# NSTRI.net
KiCad netlist of a schematic drawn in Altium Designer
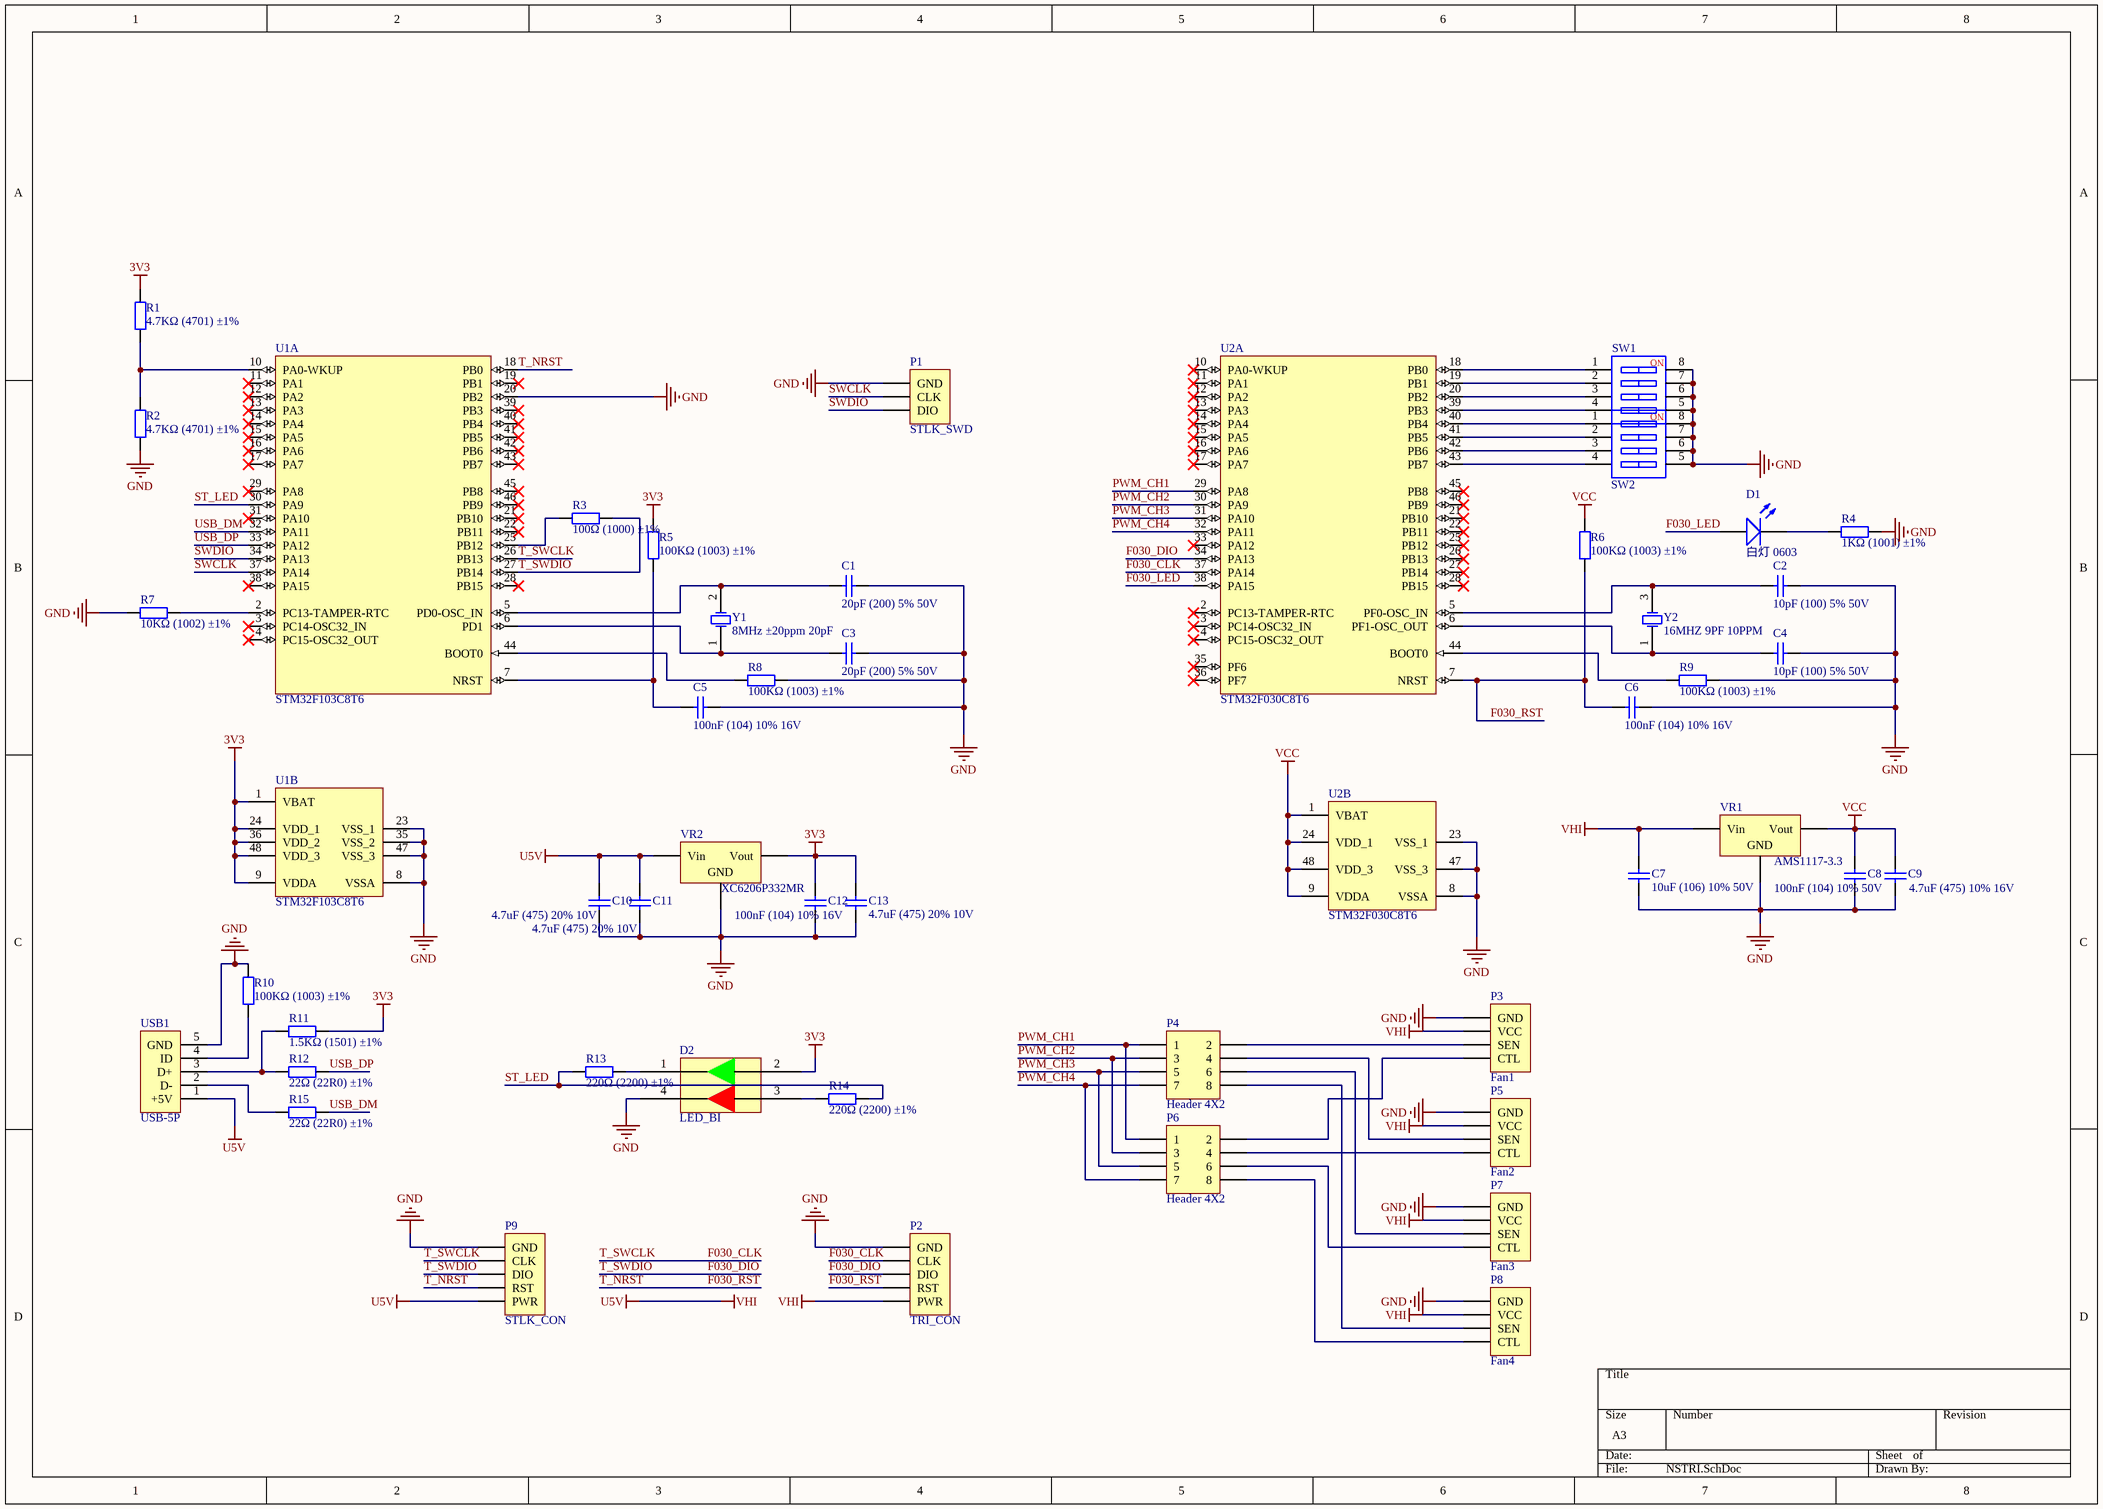
[diagram p0: NSTRI.SchDoc]

(export (version "E")
  (design (tool "Eeschema 10.0.6"))
  (components
    (comp (ref "C1")
      (value "20pF (200) 5% 50V")
      (footprint "0402_C")
      (description "贴片电容")
      (libsource (lib "Miscellaneous Devices LC") (part "0402 20pF (200) 5% 50V"))
    )
    (comp (ref "C2")
      (value "10pF (100) 5% 50V")
      (footprint "0402_C")
      (description "贴片电容")
      (libsource (lib "Miscellaneous Devices LC") (part "0402 10pF (100) 5% 50V"))
    )
    (comp (ref "C3")
      (value "20pF (200) 5% 50V")
      (footprint "0402_C")
      (description "贴片电容")
      (libsource (lib "Miscellaneous Devices LC") (part "0402 20pF (200) 5% 50V"))
    )
    (comp (ref "C4")
      (value "10pF (100) 5% 50V")
      (footprint "0402_C")
      (description "贴片电容")
      (libsource (lib "Miscellaneous Devices LC") (part "0402 10pF (100) 5% 50V"))
    )
    (comp (ref "C5")
      (value "100nF (104) 10% 16V")
      (footprint "0402_C")
      (description "贴片电容")
      (libsource (lib "Miscellaneous Devices LC") (part "0402 100nF (104) 10% 16V"))
    )
    (comp (ref "C6")
      (value "100nF (104) 10% 16V")
      (footprint "0402_C")
      (description "贴片电容")
      (libsource (lib "Miscellaneous Devices LC") (part "0402 100nF (104) 10% 16V"))
    )
    (comp (ref "C7")
      (value "10uF (106) 10% 50V")
      (footprint "1206_C")
      (description "贴片电容")
      (libsource (lib "Miscellaneous Devices LC") (part "1206 10uF (106) 10% 50V"))
    )
    (comp (ref "C8")
      (value "100nF (104) 10% 50V")
      (footprint "0603_C")
      (description "贴片电容")
      (libsource (lib "Miscellaneous Devices LC") (part "0603 100nF (104) 10% 50V"))
    )
    (comp (ref "C9")
      (value "4.7uF (475) 10% 16V")
      (footprint "0603_C")
      (description "贴片电容")
      (libsource (lib "Miscellaneous Devices LC") (part "0603 4.7uF (475) 10% 16V"))
    )
    (comp (ref "C10")
      (value "4.7uF (475) 20% 10V")
      (footprint "0402_C")
      (description "贴片电容")
      (libsource (lib "Miscellaneous Devices LC") (part "0402 4.7uF (475) 20% 10V"))
    )
    (comp (ref "C11")
      (value "4.7uF (475) 20% 10V")
      (footprint "0402_C")
      (description "贴片电容")
      (libsource (lib "Miscellaneous Devices LC") (part "0402 4.7uF (475) 20% 10V"))
    )
    (comp (ref "C12")
      (value "100nF (104) 10% 16V")
      (footprint "0402_C")
      (description "贴片电容")
      (libsource (lib "Miscellaneous Devices LC") (part "0402 100nF (104) 10% 16V"))
    )
    (comp (ref "C13")
      (value "4.7uF (475) 20% 10V")
      (footprint "0402_C")
      (description "贴片电容")
      (libsource (lib "Miscellaneous Devices LC") (part "0402 4.7uF (475) 20% 10V"))
    )
    (comp (ref "D1")
      (value "白灯 0603")
      (footprint "0603_LED_S1")
      (description "发光二极管")
      (libsource (lib "Miscellaneous Devices LC") (part "0603 白灯"))
    )
    (comp (ref "D2") (value "LED_BI") (footprint "LED_BI") (libsource (lib "ngh-util") (part "LED_BI")))
    (comp (ref "P1")
      (value "STLK_SWD")
      (footprint "HDR1X3")
      (description "Header, 3-Pin")
      (fields (field (name "PUBLISHER") "Altium Limited"))
      (libsource (lib "Miscellaneous Connectors") (part "Header 3"))
    )
    (comp (ref "P2")
      (value "TRI_CON")
      (footprint "HDR1X5")
      (description "Header, 5-Pin")
      (fields (field (name "PUBLISHER") "Altium Limited"))
      (libsource (lib "Miscellaneous Connectors") (part "Header 5"))
    )
    (comp (ref "P3")
      (value "Fan1")
      (footprint "HDR1X4")
      (description "Header, 4-Pin")
      (fields (field (name "PUBLISHER") "Altium Limited"))
      (libsource (lib "Miscellaneous Connectors") (part "Header 4"))
    )
    (comp (ref "P4")
      (value "Header 4X2")
      (footprint "HDR2X4")
      (description "Header, 4-Pin, Dual row")
      (fields (field (name "PUBLISHER") "Altium Limited"))
      (libsource (lib "Miscellaneous Connectors") (part "Header 4X2"))
    )
    (comp (ref "P5")
      (value "Fan2")
      (footprint "HDR1X4")
      (description "Header, 4-Pin")
      (fields (field (name "PUBLISHER") "Altium Limited"))
      (libsource (lib "Miscellaneous Connectors") (part "Header 4"))
    )
    (comp (ref "P6")
      (value "Header 4X2")
      (footprint "HDR2X4")
      (description "Header, 4-Pin, Dual row")
      (fields (field (name "PUBLISHER") "Altium Limited"))
      (libsource (lib "Miscellaneous Connectors") (part "Header 4X2"))
    )
    (comp (ref "P7")
      (value "Fan3")
      (footprint "HDR1X4")
      (description "Header, 4-Pin")
      (fields (field (name "PUBLISHER") "Altium Limited"))
      (libsource (lib "Miscellaneous Connectors") (part "Header 4"))
    )
    (comp (ref "P8")
      (value "Fan4")
      (footprint "HDR1X4")
      (description "Header, 4-Pin")
      (fields (field (name "PUBLISHER") "Altium Limited"))
      (libsource (lib "Miscellaneous Connectors") (part "Header 4"))
    )
    (comp (ref "P9")
      (value "STLK_CON")
      (footprint "HDR1X5")
      (description "Header, 5-Pin")
      (fields (field (name "PUBLISHER") "Altium Limited"))
      (libsource (lib "Miscellaneous Connectors") (part "Header 5"))
    )
    (comp (ref "R1")
      (value "4.7KΩ (4701) ±1%")
      (footprint "0402_R")
      (description "贴片电阻")
      (libsource (lib "Miscellaneous Devices LC") (part "0402 4.7KΩ (4701) 1%"))
    )
    (comp (ref "R2")
      (value "4.7KΩ (4701) ±1%")
      (footprint "0402_R")
      (description "贴片电阻")
      (libsource (lib "Miscellaneous Devices LC") (part "0402 4.7KΩ (4701) 1%"))
    )
    (comp (ref "R3")
      (value "100Ω (1000) ±1%")
      (footprint "0402_R")
      (description "贴片电阻")
      (libsource (lib "Miscellaneous Devices LC") (part "0402 100Ω (1000) 1%"))
    )
    (comp (ref "R4")
      (value "1KΩ (1001) ±1%")
      (footprint "0402_R")
      (description "贴片电阻")
      (libsource (lib "Miscellaneous Devices LC") (part "0402 1KΩ (1001) 1%"))
    )
    (comp (ref "R5")
      (value "100KΩ (1003) ±1%")
      (footprint "0402_R")
      (description "贴片电阻")
      (libsource (lib "Miscellaneous Devices LC") (part "0402 100KΩ (1003) 1%"))
    )
    (comp (ref "R6")
      (value "100KΩ (1003) ±1%")
      (footprint "0402_R")
      (description "贴片电阻")
      (libsource (lib "Miscellaneous Devices LC") (part "0402 100KΩ (1003) 1%"))
    )
    (comp (ref "R7")
      (value "10KΩ (1002) ±1%")
      (footprint "0402_R")
      (description "贴片电阻")
      (libsource (lib "Miscellaneous Devices LC") (part "0402 10KΩ (1002) 1%"))
    )
    (comp (ref "R8")
      (value "100KΩ (1003) ±1%")
      (footprint "0402_R")
      (description "贴片电阻")
      (libsource (lib "") (part "0402 100KΩ (1003) 1%_1"))
    )
    (comp (ref "R9")
      (value "100KΩ (1003) ±1%")
      (footprint "0402_R")
      (description "贴片电阻")
      (libsource (lib "") (part "0402 100KΩ (1003) 1%_1"))
    )
    (comp (ref "R10")
      (value "100KΩ (1003) ±1%")
      (footprint "0402_R")
      (description "贴片电阻")
      (libsource (lib "Miscellaneous Devices LC") (part "0402 100KΩ (1003) 1%"))
    )
    (comp (ref "R11")
      (value "1.5KΩ (1501) ±1%")
      (footprint "0402_R")
      (description "贴片电阻")
      (libsource (lib "Miscellaneous Devices LC") (part "0402 1.5KΩ (1501) 1%"))
    )
    (comp (ref "R12")
      (value "22Ω (22R0) ±1%")
      (footprint "0402_R")
      (description "贴片电阻")
      (libsource (lib "Miscellaneous Devices LC") (part "0402 22Ω (22R0) 1%"))
    )
    (comp (ref "R13")
      (value "220Ω (2200) ±1%")
      (footprint "0402_R")
      (description "贴片电阻")
      (libsource (lib "Miscellaneous Devices LC") (part "0402 220Ω (2200) 1%"))
    )
    (comp (ref "R14")
      (value "220Ω (2200) ±1%")
      (footprint "0402_R")
      (description "贴片电阻")
      (libsource (lib "Miscellaneous Devices LC") (part "0402 220Ω (2200) 1%"))
    )
    (comp (ref "R15")
      (value "22Ω (22R0) ±1%")
      (footprint "0402_R")
      (description "贴片电阻")
      (libsource (lib "Miscellaneous Devices LC") (part "0402 22Ω (22R0) 1%"))
    )
    (comp (ref "SW1")
      (value "CSW-4P")
      (footprint "CSW DIP-4P")
      (description "4路编码开关")
      (fields (field (name "版权归属") "源创客"))
      (libsource (lib "5.1   - 按键-开关") (part "CSW-4P"))
    )
    (comp (ref "SW2")
      (value "CSW-4P")
      (footprint "CSW DIP-4P")
      (description "4路编码开关")
      (fields (field (name "版权归属") "源创客"))
      (libsource (lib "5.1   - 按键-开关") (part "CSW-4P"))
    )
    (comp (ref "U1")
      (value "STM32F103C8T6")
      (footprint "LQFP-48_7x7x05P")
      (description "ARM")
      (libsource (lib "Miscellaneous Devices LC") (part "STM32F103C8T6"))
    )
    (comp (ref "U2")
      (value "STM32F030C8T6")
      (footprint "LQFP-48_7x7x05P")
      (description "ARM")
      (libsource (lib "STM32F030C8") (part "STM32F030C8T6"))
    )
    (comp (ref "USB1")
      (value "USB-5P")
      (footprint "USB-MICRO_D")
      (description "微型USB母座")
      (fields (field (name "版权归属") "源创客"))
      (libsource (lib "4.1   - 接口类") (part "USB-5P"))
    )
    (comp (ref "VR1")
      (value "AMS1117-3.3")
      (footprint "SOT-223")
      (description "低压差线性稳压(LDO)")
      (libsource (lib "Miscellaneous Devices LC") (part "SOT-223 AMS1117-3.3"))
    )
    (comp (ref "VR2")
      (value "XC6206P332MR")
      (footprint "SOT-23-3L")
      (description "低压差线性稳压(LDO)")
      (libsource (lib "Miscellaneous Devices LC") (part "SOT-23 XC6206P332MR"))
    )
    (comp (ref "Y1")
      (value "8MHz ±20ppm 20pF")
      (footprint "SMD-5032_2P")
      (description "贴片晶振")
      (libsource (lib "Miscellaneous Devices LC") (part "SMD-5032_2P 8MHz 20ppm 20pF"))
    )
    (comp (ref "Y2")
      (value "16MHZ 9PF 10PPM")
      (footprint "SMD-3225_4P")
      (description "贴片晶振")
      (libsource (lib "Miscellaneous Devices LC") (part "SMD-3225_4P  16MHZ 9PF 10PPM"))
    )
  )
  (nets
    (net (code "1") (name "/F030_CLK") (class "Default")
      (node (ref "P2") (pin "2") (pinfunction "CLK_2") (pintype "passive"))
      (node (ref "P9") (pin "2") (pinfunction "CLK_2") (pintype "passive"))
      (node (ref "U1") (pin "26") (pinfunction "PB13_26") (pintype "bidirectional"))
      (node (ref "U2") (pin "37") (pinfunction "PA14_37") (pintype "bidirectional"))
    )
    (net (code "2") (name "/F030_DIO") (class "Default")
      (node (ref "P2") (pin "3") (pinfunction "DIO_3") (pintype "passive"))
      (node (ref "P9") (pin "3") (pinfunction "DIO_3") (pintype "passive"))
      (node (ref "R3") (pin "2") (pinfunction "2_2") (pintype "passive"))
      (node (ref "U1") (pin "27") (pinfunction "PB14_27") (pintype "bidirectional"))
      (node (ref "U2") (pin "34") (pinfunction "PA13_34") (pintype "bidirectional"))
    )
    (net (code "3") (name "/F030_LED") (class "Default")
      (node (ref "D1") (pin "A") (pinfunction "A_A") (pintype "passive"))
      (node (ref "U2") (pin "38") (pinfunction "PA15_38") (pintype "bidirectional"))
    )
    (net (code "4") (name "/F030_RST") (class "Default")
      (node (ref "C6") (pin "2") (pinfunction "2_2") (pintype "passive"))
      (node (ref "P2") (pin "4") (pinfunction "RST_4") (pintype "passive"))
      (node (ref "P9") (pin "4") (pinfunction "RST_4") (pintype "passive"))
      (node (ref "R6") (pin "1") (pinfunction "1_1") (pintype "passive"))
      (node (ref "U1") (pin "18") (pinfunction "PB0_18") (pintype "bidirectional"))
      (node (ref "U2") (pin "7") (pinfunction "NRST_7") (pintype "bidirectional"))
    )
    (net (code "5") (name "/PWM_CH1") (class "Default")
      (node (ref "P4") (pin "1") (pinfunction "1_1") (pintype "passive"))
      (node (ref "P6") (pin "1") (pinfunction "1_1") (pintype "passive"))
      (node (ref "U2") (pin "29") (pinfunction "PA8_29") (pintype "bidirectional"))
    )
    (net (code "6") (name "/PWM_CH2") (class "Default")
      (node (ref "P4") (pin "3") (pinfunction "3_3") (pintype "passive"))
      (node (ref "P6") (pin "3") (pinfunction "3_3") (pintype "passive"))
      (node (ref "U2") (pin "30") (pinfunction "PA9_30") (pintype "bidirectional"))
    )
    (net (code "7") (name "/PWM_CH3") (class "Default")
      (node (ref "P4") (pin "5") (pinfunction "5_5") (pintype "passive"))
      (node (ref "P6") (pin "5") (pinfunction "5_5") (pintype "passive"))
      (node (ref "U2") (pin "31") (pinfunction "PA10_31") (pintype "bidirectional"))
    )
    (net (code "8") (name "/PWM_CH4") (class "Default")
      (node (ref "P4") (pin "7") (pinfunction "7_7") (pintype "passive"))
      (node (ref "P6") (pin "7") (pinfunction "7_7") (pintype "passive"))
      (node (ref "U2") (pin "32") (pinfunction "PA11_32") (pintype "bidirectional"))
    )
    (net (code "9") (name "/ST_LED") (class "Default")
      (node (ref "R13") (pin "1") (pinfunction "1_1") (pintype "passive"))
      (node (ref "R14") (pin "2") (pinfunction "2_2") (pintype "passive"))
      (node (ref "U1") (pin "30") (pinfunction "PA9_30") (pintype "bidirectional"))
    )
    (net (code "10") (name "/SWCLK") (class "Default")
      (node (ref "P1") (pin "2") (pinfunction "CLK_2") (pintype "passive"))
      (node (ref "U1") (pin "37") (pinfunction "PA14_37") (pintype "bidirectional"))
    )
    (net (code "11") (name "/SWDIO") (class "Default")
      (node (ref "P1") (pin "3") (pinfunction "DIO_3") (pintype "passive"))
      (node (ref "U1") (pin "34") (pinfunction "PA13_34") (pintype "bidirectional"))
    )
    (net (code "12") (name "/USB_DM") (class "Default")
      (node (ref "R15") (pin "2") (pinfunction "2_2") (pintype "passive"))
      (node (ref "U1") (pin "32") (pinfunction "PA11_32") (pintype "bidirectional"))
    )
    (net (code "13") (name "/USB_DP") (class "Default")
      (node (ref "R12") (pin "2") (pinfunction "2_2") (pintype "passive"))
      (node (ref "U1") (pin "33") (pinfunction "PA12_33") (pintype "bidirectional"))
    )
    (net (code "14") (name "3V3") (class "Default")
      (node (ref "C12") (pin "2") (pinfunction "2_2") (pintype "passive"))
      (node (ref "C13") (pin "2") (pinfunction "2_2") (pintype "passive"))
      (node (ref "D2") (pin "2") (pinfunction "2_2") (pintype "passive"))
      (node (ref "R1") (pin "2") (pinfunction "2_2") (pintype "passive"))
      (node (ref "R11") (pin "2") (pinfunction "2_2") (pintype "passive"))
      (node (ref "R5") (pin "2") (pinfunction "2_2") (pintype "passive"))
      (node (ref "U1") (pin "1") (pinfunction "VBAT_1") (pintype "power_in"))
      (node (ref "U1") (pin "24") (pinfunction "VDD_1_24") (pintype "power_in"))
      (node (ref "U1") (pin "36") (pinfunction "VDD_2_36") (pintype "power_in"))
      (node (ref "U1") (pin "48") (pinfunction "VDD_3_48") (pintype "power_in"))
      (node (ref "U1") (pin "9") (pinfunction "VDDA_9") (pintype "power_in"))
      (node (ref "VR2") (pin "2") (pinfunction "Vout_2") (pintype "passive"))
    )
    (net (code "15") (name "GND") (class "Default")
      (node (ref "C1") (pin "2") (pinfunction "2_2") (pintype "passive"))
      (node (ref "C10") (pin "1") (pinfunction "1_1") (pintype "passive"))
      (node (ref "C11") (pin "1") (pinfunction "1_1") (pintype "passive"))
      (node (ref "C12") (pin "1") (pinfunction "1_1") (pintype "passive"))
      (node (ref "C13") (pin "1") (pinfunction "1_1") (pintype "passive"))
      (node (ref "C2") (pin "2") (pinfunction "2_2") (pintype "passive"))
      (node (ref "C3") (pin "2") (pinfunction "2_2") (pintype "passive"))
      (node (ref "C4") (pin "2") (pinfunction "2_2") (pintype "passive"))
      (node (ref "C5") (pin "1") (pinfunction "1_1") (pintype "passive"))
      (node (ref "C6") (pin "1") (pinfunction "1_1") (pintype "passive"))
      (node (ref "C7") (pin "1") (pinfunction "1_1") (pintype "passive"))
      (node (ref "C8") (pin "1") (pinfunction "1_1") (pintype "passive"))
      (node (ref "C9") (pin "1") (pinfunction "1_1") (pintype "passive"))
      (node (ref "D2") (pin "4") (pinfunction "4_4") (pintype "passive"))
      (node (ref "P1") (pin "1") (pinfunction "GND_1") (pintype "passive"))
      (node (ref "P2") (pin "1") (pinfunction "GND_1") (pintype "passive"))
      (node (ref "P3") (pin "1") (pinfunction "GND_1") (pintype "passive"))
      (node (ref "P5") (pin "1") (pinfunction "GND_1") (pintype "passive"))
      (node (ref "P7") (pin "1") (pinfunction "GND_1") (pintype "passive"))
      (node (ref "P8") (pin "1") (pinfunction "GND_1") (pintype "passive"))
      (node (ref "P9") (pin "1") (pinfunction "GND_1") (pintype "passive"))
      (node (ref "R10") (pin "2") (pinfunction "2_2") (pintype "passive"))
      (node (ref "R2") (pin "1") (pinfunction "1_1") (pintype "passive"))
      (node (ref "R4") (pin "2") (pinfunction "2_2") (pintype "passive"))
      (node (ref "R7") (pin "1") (pinfunction "1_1") (pintype "passive"))
      (node (ref "R8") (pin "2") (pinfunction "2_2") (pintype "passive"))
      (node (ref "R9") (pin "2") (pinfunction "2_2") (pintype "passive"))
      (node (ref "SW1") (pin "5") (pinfunction "5_5") (pintype "passive"))
      (node (ref "SW1") (pin "6") (pinfunction "6_6") (pintype "passive"))
      (node (ref "SW1") (pin "7") (pinfunction "7_7") (pintype "passive"))
      (node (ref "SW1") (pin "8") (pinfunction "8_8") (pintype "passive"))
      (node (ref "SW2") (pin "5") (pinfunction "5_5") (pintype "passive"))
      (node (ref "SW2") (pin "6") (pinfunction "6_6") (pintype "passive"))
      (node (ref "SW2") (pin "7") (pinfunction "7_7") (pintype "passive"))
      (node (ref "SW2") (pin "8") (pinfunction "8_8") (pintype "passive"))
      (node (ref "U1") (pin "20") (pinfunction "PB2_20") (pintype "bidirectional"))
      (node (ref "U1") (pin "23") (pinfunction "VSS_1_23") (pintype "power_in"))
      (node (ref "U1") (pin "35") (pinfunction "VSS_2_35") (pintype "power_in"))
      (node (ref "U1") (pin "47") (pinfunction "VSS_3_47") (pintype "power_in"))
      (node (ref "U1") (pin "8") (pinfunction "VSSA_8") (pintype "power_in"))
      (node (ref "U2") (pin "23") (pinfunction "VSS_1_23") (pintype "power_in"))
      (node (ref "U2") (pin "47") (pinfunction "VSS_3_47") (pintype "power_in"))
      (node (ref "U2") (pin "8") (pinfunction "VSSA_8") (pintype "power_in"))
      (node (ref "USB1") (pin "5") (pinfunction "GND_5") (pintype "passive"))
      (node (ref "VR1") (pin "1") (pinfunction "GND_1") (pintype "passive"))
      (node (ref "VR2") (pin "1") (pinfunction "GND_1") (pintype "passive"))
    )
    (net (code "16") (name "Net-(D1-PadK)") (class "Default")
      (node (ref "D1") (pin "K") (pinfunction "K_K") (pintype "passive"))
      (node (ref "R4") (pin "1") (pinfunction "1_1") (pintype "passive"))
    )
    (net (code "17") (name "Net-(D2-Pad1)") (class "Default")
      (node (ref "D2") (pin "1") (pinfunction "1_1") (pintype "passive"))
      (node (ref "R13") (pin "2") (pinfunction "2_2") (pintype "passive"))
    )
    (net (code "18") (name "Net-(D2-Pad3)") (class "Default")
      (node (ref "D2") (pin "3") (pinfunction "3_3") (pintype "passive"))
      (node (ref "R14") (pin "1") (pinfunction "1_1") (pintype "passive"))
    )
    (net (code "19") (name "Net-(P3-CTL)") (class "Default")
      (node (ref "P3") (pin "4") (pinfunction "CTL_4") (pintype "passive"))
      (node (ref "P6") (pin "2") (pinfunction "2_2") (pintype "passive"))
    )
    (net (code "20") (name "Net-(P3-SEN)") (class "Default")
      (node (ref "P3") (pin "3") (pinfunction "SEN_3") (pintype "passive"))
      (node (ref "P4") (pin "2") (pinfunction "2_2") (pintype "passive"))
    )
    (net (code "21") (name "Net-(P5-CTL)") (class "Default")
      (node (ref "P5") (pin "4") (pinfunction "CTL_4") (pintype "passive"))
      (node (ref "P6") (pin "4") (pinfunction "4_4") (pintype "passive"))
    )
    (net (code "22") (name "Net-(P5-SEN)") (class "Default")
      (node (ref "P4") (pin "4") (pinfunction "4_4") (pintype "passive"))
      (node (ref "P5") (pin "3") (pinfunction "SEN_3") (pintype "passive"))
    )
    (net (code "23") (name "Net-(P7-CTL)") (class "Default")
      (node (ref "P6") (pin "6") (pinfunction "6_6") (pintype "passive"))
      (node (ref "P7") (pin "4") (pinfunction "CTL_4") (pintype "passive"))
    )
    (net (code "24") (name "Net-(P7-SEN)") (class "Default")
      (node (ref "P4") (pin "6") (pinfunction "6_6") (pintype "passive"))
      (node (ref "P7") (pin "3") (pinfunction "SEN_3") (pintype "passive"))
    )
    (net (code "25") (name "Net-(P8-CTL)") (class "Default")
      (node (ref "P6") (pin "8") (pinfunction "8_8") (pintype "passive"))
      (node (ref "P8") (pin "4") (pinfunction "CTL_4") (pintype "passive"))
    )
    (net (code "26") (name "Net-(P8-SEN)") (class "Default")
      (node (ref "P4") (pin "8") (pinfunction "8_8") (pintype "passive"))
      (node (ref "P8") (pin "3") (pinfunction "SEN_3") (pintype "passive"))
    )
    (net (code "27") (name "Net-(U1A-BOOT0)") (class "Default")
      (node (ref "R8") (pin "1") (pinfunction "1_1") (pintype "passive"))
      (node (ref "U1") (pin "44") (pinfunction "BOOT0_44") (pintype "input"))
    )
    (net (code "28") (name "Net-(U1A-NRST)") (class "Default")
      (node (ref "C5") (pin "2") (pinfunction "2_2") (pintype "passive"))
      (node (ref "R5") (pin "1") (pinfunction "1_1") (pintype "passive"))
      (node (ref "U1") (pin "7") (pinfunction "NRST_7") (pintype "bidirectional"))
    )
    (net (code "29") (name "Net-(U1A-PA0-WKUP)") (class "Default")
      (node (ref "R1") (pin "1") (pinfunction "1_1") (pintype "passive"))
      (node (ref "R2") (pin "2") (pinfunction "2_2") (pintype "passive"))
      (node (ref "U1") (pin "10") (pinfunction "PA0-WKUP_10") (pintype "bidirectional"))
    )
    (net (code "30") (name "Net-(U1A-PB12)") (class "Default")
      (node (ref "R3") (pin "1") (pinfunction "1_1") (pintype "passive"))
      (node (ref "U1") (pin "25") (pinfunction "PB12_25") (pintype "bidirectional"))
    )
    (net (code "31") (name "Net-(U1A-PC13-TAMPER-RTC)") (class "Default")
      (node (ref "R7") (pin "2") (pinfunction "2_2") (pintype "passive"))
      (node (ref "U1") (pin "2") (pinfunction "PC13-TAMPER-RTC_2") (pintype "bidirectional"))
    )
    (net (code "32") (name "Net-(U1A-PD0-OSC_IN)") (class "Default")
      (node (ref "C1") (pin "1") (pinfunction "1_1") (pintype "passive"))
      (node (ref "U1") (pin "5") (pinfunction "PD0-OSC_IN_5") (pintype "bidirectional"))
      (node (ref "Y1") (pin "2") (pinfunction "OSC2_2") (pintype "passive"))
    )
    (net (code "33") (name "Net-(U1A-PD1)") (class "Default")
      (node (ref "C3") (pin "1") (pinfunction "1_1") (pintype "passive"))
      (node (ref "U1") (pin "6") (pinfunction "PD1_6") (pintype "bidirectional"))
      (node (ref "Y1") (pin "1") (pinfunction "OSC1_1") (pintype "passive"))
    )
    (net (code "34") (name "Net-(U2A-BOOT0)") (class "Default")
      (node (ref "R9") (pin "1") (pinfunction "1_1") (pintype "passive"))
      (node (ref "U2") (pin "44") (pinfunction "BOOT0_44") (pintype "input"))
    )
    (net (code "35") (name "Net-(U2A-PB0)") (class "Default")
      (node (ref "SW1") (pin "1") (pinfunction "1_1") (pintype "passive"))
      (node (ref "U2") (pin "18") (pinfunction "PB0_18") (pintype "bidirectional"))
    )
    (net (code "36") (name "Net-(U2A-PB1)") (class "Default")
      (node (ref "SW1") (pin "2") (pinfunction "2_2") (pintype "passive"))
      (node (ref "U2") (pin "19") (pinfunction "PB1_19") (pintype "bidirectional"))
    )
    (net (code "37") (name "Net-(U2A-PB2)") (class "Default")
      (node (ref "SW1") (pin "3") (pinfunction "3_3") (pintype "passive"))
      (node (ref "U2") (pin "20") (pinfunction "PB2_20") (pintype "bidirectional"))
    )
    (net (code "38") (name "Net-(U2A-PB3)") (class "Default")
      (node (ref "SW1") (pin "4") (pinfunction "4_4") (pintype "passive"))
      (node (ref "U2") (pin "39") (pinfunction "PB3_39") (pintype "bidirectional"))
    )
    (net (code "39") (name "Net-(U2A-PB4)") (class "Default")
      (node (ref "SW2") (pin "1") (pinfunction "1_1") (pintype "passive"))
      (node (ref "U2") (pin "40") (pinfunction "PB4_40") (pintype "bidirectional"))
    )
    (net (code "40") (name "Net-(U2A-PB5)") (class "Default")
      (node (ref "SW2") (pin "2") (pinfunction "2_2") (pintype "passive"))
      (node (ref "U2") (pin "41") (pinfunction "PB5_41") (pintype "bidirectional"))
    )
    (net (code "41") (name "Net-(U2A-PB6)") (class "Default")
      (node (ref "SW2") (pin "3") (pinfunction "3_3") (pintype "passive"))
      (node (ref "U2") (pin "42") (pinfunction "PB6_42") (pintype "bidirectional"))
    )
    (net (code "42") (name "Net-(U2A-PB7)") (class "Default")
      (node (ref "SW2") (pin "4") (pinfunction "4_4") (pintype "passive"))
      (node (ref "U2") (pin "43") (pinfunction "PB7_43") (pintype "bidirectional"))
    )
    (net (code "43") (name "Net-(U2A-PF0-OSC_IN)") (class "Default")
      (node (ref "C2") (pin "1") (pinfunction "1_1") (pintype "passive"))
      (node (ref "U2") (pin "5") (pinfunction "PF0-OSC_IN_5") (pintype "bidirectional"))
      (node (ref "Y2") (pin "3") (pinfunction "OSC2_3") (pintype "passive"))
    )
    (net (code "44") (name "Net-(U2A-PF1-OSC_OUT)") (class "Default")
      (node (ref "C4") (pin "1") (pinfunction "1_1") (pintype "passive"))
      (node (ref "U2") (pin "6") (pinfunction "PF1-OSC_OUT_6") (pintype "bidirectional"))
      (node (ref "Y2") (pin "1") (pinfunction "OSC1_1") (pintype "passive"))
    )
    (net (code "45") (name "Net-(USB1-D+)") (class "Default")
      (node (ref "R11") (pin "1") (pinfunction "1_1") (pintype "passive"))
      (node (ref "R12") (pin "1") (pinfunction "1_1") (pintype "passive"))
      (node (ref "USB1") (pin "3") (pinfunction "D+_3") (pintype "passive"))
    )
    (net (code "46") (name "Net-(USB1-D-)") (class "Default")
      (node (ref "R15") (pin "1") (pinfunction "1_1") (pintype "passive"))
      (node (ref "USB1") (pin "2") (pinfunction "D-_2") (pintype "passive"))
    )
    (net (code "47") (name "Net-(USB1-ID)") (class "Default")
      (node (ref "R10") (pin "1") (pinfunction "1_1") (pintype "passive"))
      (node (ref "USB1") (pin "4") (pinfunction "ID_4") (pintype "passive"))
    )
    (net (code "48") (name "U5V") (class "Default")
      (node (ref "C10") (pin "2") (pinfunction "2_2") (pintype "passive"))
      (node (ref "C11") (pin "2") (pinfunction "2_2") (pintype "passive"))
      (node (ref "C7") (pin "2") (pinfunction "2_2") (pintype "passive"))
      (node (ref "P2") (pin "5") (pinfunction "PWR_5") (pintype "passive"))
      (node (ref "P3") (pin "2") (pinfunction "VCC_2") (pintype "passive"))
      (node (ref "P5") (pin "2") (pinfunction "VCC_2") (pintype "passive"))
      (node (ref "P7") (pin "2") (pinfunction "VCC_2") (pintype "passive"))
      (node (ref "P8") (pin "2") (pinfunction "VCC_2") (pintype "passive"))
      (node (ref "P9") (pin "5") (pinfunction "PWR_5") (pintype "passive"))
      (node (ref "USB1") (pin "1") (pinfunction "+5V_1") (pintype "passive"))
      (node (ref "VR1") (pin "3") (pinfunction "Vin_3") (pintype "passive"))
      (node (ref "VR2") (pin "3") (pinfunction "Vin_3") (pintype "passive"))
    )
    (net (code "49") (name "VCC") (class "Default")
      (node (ref "C8") (pin "2") (pinfunction "2_2") (pintype "passive"))
      (node (ref "C9") (pin "2") (pinfunction "2_2") (pintype "passive"))
      (node (ref "R6") (pin "2") (pinfunction "2_2") (pintype "passive"))
      (node (ref "U2") (pin "1") (pinfunction "VBAT_1") (pintype "power_in"))
      (node (ref "U2") (pin "24") (pinfunction "VDD_1_24") (pintype "power_in"))
      (node (ref "U2") (pin "48") (pinfunction "VDD_3_48") (pintype "power_in"))
      (node (ref "U2") (pin "9") (pinfunction "VDDA_9") (pintype "power_in"))
      (node (ref "VR1") (pin "2") (pinfunction "Vout_2") (pintype "passive"))
    )
    (net (code "50") (name "unconnected-(U1A-PA1-Pad11)") (class "Default")
      (node (ref "U1") (pin "11") (pinfunction "PA1_11") (pintype "bidirectional+no_connect"))
    )
    (net (code "51") (name "unconnected-(U1A-PA2-Pad12)") (class "Default")
      (node (ref "U1") (pin "12") (pinfunction "PA2_12") (pintype "bidirectional+no_connect"))
    )
    (net (code "52") (name "unconnected-(U1A-PA3-Pad13)") (class "Default")
      (node (ref "U1") (pin "13") (pinfunction "PA3_13") (pintype "bidirectional+no_connect"))
    )
    (net (code "53") (name "unconnected-(U1A-PA4-Pad14)") (class "Default")
      (node (ref "U1") (pin "14") (pinfunction "PA4_14") (pintype "bidirectional+no_connect"))
    )
    (net (code "54") (name "unconnected-(U1A-PA5-Pad15)") (class "Default")
      (node (ref "U1") (pin "15") (pinfunction "PA5_15") (pintype "bidirectional+no_connect"))
    )
    (net (code "55") (name "unconnected-(U1A-PA6-Pad16)") (class "Default")
      (node (ref "U1") (pin "16") (pinfunction "PA6_16") (pintype "bidirectional+no_connect"))
    )
    (net (code "56") (name "unconnected-(U1A-PA7-Pad17)") (class "Default")
      (node (ref "U1") (pin "17") (pinfunction "PA7_17") (pintype "bidirectional+no_connect"))
    )
    (net (code "57") (name "unconnected-(U1A-PA8-Pad29)") (class "Default")
      (node (ref "U1") (pin "29") (pinfunction "PA8_29") (pintype "bidirectional+no_connect"))
    )
    (net (code "58") (name "unconnected-(U1A-PA10-Pad31)") (class "Default")
      (node (ref "U1") (pin "31") (pinfunction "PA10_31") (pintype "bidirectional+no_connect"))
    )
    (net (code "59") (name "unconnected-(U1A-PA15-Pad38)") (class "Default")
      (node (ref "U1") (pin "38") (pinfunction "PA15_38") (pintype "bidirectional+no_connect"))
    )
    (net (code "60") (name "unconnected-(U1A-PB1-Pad19)") (class "Default")
      (node (ref "U1") (pin "19") (pinfunction "PB1_19") (pintype "bidirectional+no_connect"))
    )
    (net (code "61") (name "unconnected-(U1A-PB3-Pad39)") (class "Default")
      (node (ref "U1") (pin "39") (pinfunction "PB3_39") (pintype "bidirectional+no_connect"))
    )
    (net (code "62") (name "unconnected-(U1A-PB4-Pad40)") (class "Default")
      (node (ref "U1") (pin "40") (pinfunction "PB4_40") (pintype "bidirectional+no_connect"))
    )
    (net (code "63") (name "unconnected-(U1A-PB5-Pad41)") (class "Default")
      (node (ref "U1") (pin "41") (pinfunction "PB5_41") (pintype "bidirectional+no_connect"))
    )
    (net (code "64") (name "unconnected-(U1A-PB6-Pad42)") (class "Default")
      (node (ref "U1") (pin "42") (pinfunction "PB6_42") (pintype "bidirectional+no_connect"))
    )
    (net (code "65") (name "unconnected-(U1A-PB7-Pad43)") (class "Default")
      (node (ref "U1") (pin "43") (pinfunction "PB7_43") (pintype "bidirectional+no_connect"))
    )
    (net (code "66") (name "unconnected-(U1A-PB8-Pad45)") (class "Default")
      (node (ref "U1") (pin "45") (pinfunction "PB8_45") (pintype "bidirectional+no_connect"))
    )
    (net (code "67") (name "unconnected-(U1A-PB9-Pad46)") (class "Default")
      (node (ref "U1") (pin "46") (pinfunction "PB9_46") (pintype "bidirectional+no_connect"))
    )
    (net (code "68") (name "unconnected-(U1A-PB10-Pad21)") (class "Default")
      (node (ref "U1") (pin "21") (pinfunction "PB10_21") (pintype "bidirectional+no_connect"))
    )
    (net (code "69") (name "unconnected-(U1A-PB11-Pad22)") (class "Default")
      (node (ref "U1") (pin "22") (pinfunction "PB11_22") (pintype "bidirectional+no_connect"))
    )
    (net (code "70") (name "unconnected-(U1A-PB15-Pad28)") (class "Default")
      (node (ref "U1") (pin "28") (pinfunction "PB15_28") (pintype "bidirectional+no_connect"))
    )
    (net (code "71") (name "unconnected-(U1A-PC14-OSC32_IN-Pad3)") (class "Default")
      (node (ref "U1") (pin "3") (pinfunction "PC14-OSC32_IN_3") (pintype "bidirectional+no_connect"))
    )
    (net (code "72") (name "unconnected-(U1A-PC15-OSC32_OUT-Pad4)") (class "Default")
      (node (ref "U1") (pin "4") (pinfunction "PC15-OSC32_OUT_4") (pintype "bidirectional+no_connect"))
    )
    (net (code "73") (name "unconnected-(U2A-PA0-WKUP-Pad10)") (class "Default")
      (node (ref "U2") (pin "10") (pinfunction "PA0-WKUP_10") (pintype "bidirectional+no_connect"))
    )
    (net (code "74") (name "unconnected-(U2A-PA1-Pad11)") (class "Default")
      (node (ref "U2") (pin "11") (pinfunction "PA1_11") (pintype "bidirectional+no_connect"))
    )
    (net (code "75") (name "unconnected-(U2A-PA2-Pad12)") (class "Default")
      (node (ref "U2") (pin "12") (pinfunction "PA2_12") (pintype "bidirectional+no_connect"))
    )
    (net (code "76") (name "unconnected-(U2A-PA3-Pad13)") (class "Default")
      (node (ref "U2") (pin "13") (pinfunction "PA3_13") (pintype "bidirectional+no_connect"))
    )
    (net (code "77") (name "unconnected-(U2A-PA4-Pad14)") (class "Default")
      (node (ref "U2") (pin "14") (pinfunction "PA4_14") (pintype "bidirectional+no_connect"))
    )
    (net (code "78") (name "unconnected-(U2A-PA5-Pad15)") (class "Default")
      (node (ref "U2") (pin "15") (pinfunction "PA5_15") (pintype "bidirectional+no_connect"))
    )
    (net (code "79") (name "unconnected-(U2A-PA6-Pad16)") (class "Default")
      (node (ref "U2") (pin "16") (pinfunction "PA6_16") (pintype "bidirectional+no_connect"))
    )
    (net (code "80") (name "unconnected-(U2A-PA7-Pad17)") (class "Default")
      (node (ref "U2") (pin "17") (pinfunction "PA7_17") (pintype "bidirectional+no_connect"))
    )
    (net (code "81") (name "unconnected-(U2A-PA12-Pad33)") (class "Default")
      (node (ref "U2") (pin "33") (pinfunction "PA12_33") (pintype "bidirectional+no_connect"))
    )
    (net (code "82") (name "unconnected-(U2A-PB8-Pad45)") (class "Default")
      (node (ref "U2") (pin "45") (pinfunction "PB8_45") (pintype "bidirectional+no_connect"))
    )
    (net (code "83") (name "unconnected-(U2A-PB9-Pad46)") (class "Default")
      (node (ref "U2") (pin "46") (pinfunction "PB9_46") (pintype "bidirectional+no_connect"))
    )
    (net (code "84") (name "unconnected-(U2A-PB10-Pad21)") (class "Default")
      (node (ref "U2") (pin "21") (pinfunction "PB10_21") (pintype "bidirectional+no_connect"))
    )
    (net (code "85") (name "unconnected-(U2A-PB11-Pad22)") (class "Default")
      (node (ref "U2") (pin "22") (pinfunction "PB11_22") (pintype "bidirectional+no_connect"))
    )
    (net (code "86") (name "unconnected-(U2A-PB12-Pad25)") (class "Default")
      (node (ref "U2") (pin "25") (pinfunction "PB12_25") (pintype "bidirectional+no_connect"))
    )
    (net (code "87") (name "unconnected-(U2A-PB13-Pad26)") (class "Default")
      (node (ref "U2") (pin "26") (pinfunction "PB13_26") (pintype "bidirectional+no_connect"))
    )
    (net (code "88") (name "unconnected-(U2A-PB14-Pad27)") (class "Default")
      (node (ref "U2") (pin "27") (pinfunction "PB14_27") (pintype "bidirectional+no_connect"))
    )
    (net (code "89") (name "unconnected-(U2A-PB15-Pad28)") (class "Default")
      (node (ref "U2") (pin "28") (pinfunction "PB15_28") (pintype "bidirectional+no_connect"))
    )
    (net (code "90") (name "unconnected-(U2A-PC13-TAMPER-RTC-Pad2)") (class "Default")
      (node (ref "U2") (pin "2") (pinfunction "PC13-TAMPER-RTC_2") (pintype "bidirectional+no_connect"))
    )
    (net (code "91") (name "unconnected-(U2A-PC14-OSC32_IN-Pad3)") (class "Default")
      (node (ref "U2") (pin "3") (pinfunction "PC14-OSC32_IN_3") (pintype "bidirectional+no_connect"))
    )
    (net (code "92") (name "unconnected-(U2A-PC15-OSC32_OUT-Pad4)") (class "Default")
      (node (ref "U2") (pin "4") (pinfunction "PC15-OSC32_OUT_4") (pintype "bidirectional+no_connect"))
    )
    (net (code "93") (name "unconnected-(U2A-PF6-Pad35)") (class "Default")
      (node (ref "U2") (pin "35") (pinfunction "PF6_35") (pintype "bidirectional+no_connect"))
    )
    (net (code "94") (name "unconnected-(U2A-PF7-Pad36)") (class "Default")
      (node (ref "U2") (pin "36") (pinfunction "PF7_36") (pintype "bidirectional+no_connect"))
    )
  )
)
